# Sheet1.net
KiCad netlist of a schematic drawn in Altium Designer
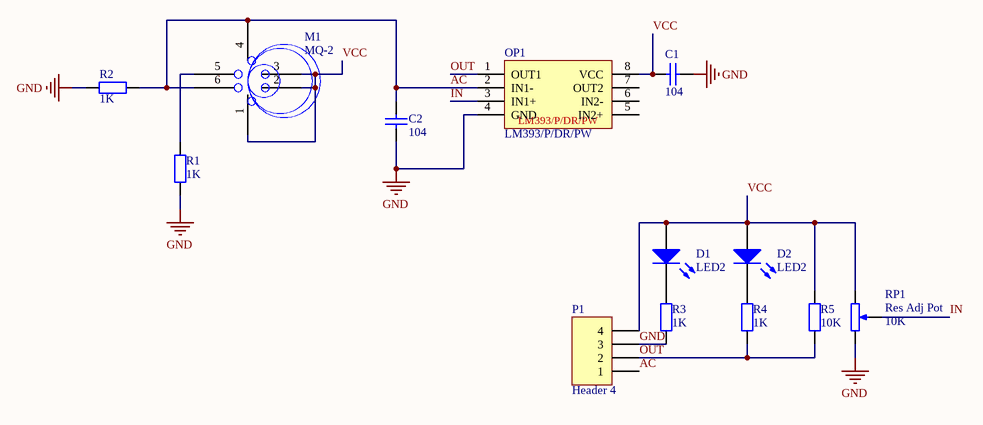
[diagram p0: Sheet1.SchDoc]

(export (version "E")
  (design (tool "Eeschema 10.0.6"))
  (components
    (comp (ref "C1")
      (value "104")
      (footprint "CC2012-0805")
      (description "Polarized Capacitor (Radial)")
      (fields (field (name "Comment") "Cap Chip 0805") (field (name "PUBLISHER") "Altium Limited"))
      (libsource (lib "EButterflyIntegratedLibrary") (part "Cap Chip 0805"))
    )
    (comp (ref "C2")
      (value "104")
      (footprint "CC2012-0805")
      (description "Polarized Capacitor (Radial)")
      (fields (field (name "Comment") "Cap Chip 0805") (field (name "PUBLISHER") "Altium Limited"))
      (libsource (lib "EButterflyIntegratedLibrary") (part "Cap Chip 0805"))
    )
    (comp (ref "D1")
      (value "LED2")
      (footprint "3.2X1.6X1.1")
      (description "Typical RED, GREEN, YELLOW, AMBER GaAs LED")
      (fields (field (name "PUBLISHER") "Altium Limited"))
      (libsource (lib "Miscellaneous Devices") (part "LED2"))
    )
    (comp (ref "D2")
      (value "LED2")
      (footprint "3.2X1.6X1.1")
      (description "Typical RED, GREEN, YELLOW, AMBER GaAs LED")
      (fields (field (name "PUBLISHER") "Altium Limited"))
      (libsource (lib "Miscellaneous Devices") (part "LED2"))
    )
    (comp (ref "M1") (value "MQ-2") (footprint "PCBComponent_1") (libsource (lib "传感器") (part "MQ-2")))
    (comp (ref "OP1")
      (value "LM393/P/DR/PW")
      (footprint "DIP-8")
      (libsource (lib "运放器件") (part "LM393/P/DR/PW"))
    )
    (comp (ref "P1")
      (value "Header 4")
      (footprint "HDR1X4")
      (description "Header, 4-Pin")
      (fields (field (name "PUBLISHER") "Altium Limited"))
      (libsource (lib "Miscellaneous Connectors") (part "Header 4"))
    )
    (comp (ref "R1")
      (value "1K")
      (footprint "CR2012-0805")
      (description "Resistor")
      (fields (field (name "Comment") "Resistor Chip 0805") (field (name "PUBLISHER") "Altium Limited"))
      (libsource (lib "EButterflyIntegratedLibrary") (part "Resistor Chip 0805"))
    )
    (comp (ref "R2")
      (value "1K")
      (footprint "CR2012-0805")
      (description "Resistor")
      (fields (field (name "Comment") "Resistor Chip 0805") (field (name "PUBLISHER") "Altium Limited"))
      (libsource (lib "") (part "Resistor Chip 0805_1"))
    )
    (comp (ref "R3")
      (value "1K")
      (footprint "CR2012-0805")
      (description "Resistor")
      (fields (field (name "Comment") "Resistor Chip 0805") (field (name "PUBLISHER") "Altium Limited"))
      (libsource (lib "EButterflyIntegratedLibrary") (part "Resistor Chip 0805"))
    )
    (comp (ref "R4")
      (value "1K")
      (footprint "CR2012-0805")
      (description "Resistor")
      (fields (field (name "Comment") "Resistor Chip 0805") (field (name "PUBLISHER") "Altium Limited"))
      (libsource (lib "EButterflyIntegratedLibrary") (part "Resistor Chip 0805"))
    )
    (comp (ref "R5")
      (value "10K")
      (footprint "CR2012-0805")
      (description "Resistor")
      (fields (field (name "Comment") "Resistor Chip 0805") (field (name "PUBLISHER") "Altium Limited"))
      (libsource (lib "EButterflyIntegratedLibrary") (part "Resistor Chip 0805"))
    )
    (comp (ref "RP1")
      (value "Res Adj Pot")
      (footprint "POT BIG")
      (description "Potentiometer")
      (fields (field (name "ALTIUM_VALUE") "10K") (field (name "PUBLISHER") "Altium Limited"))
      (libsource (lib "EButterflyIntegratedLibrary") (part "Res Adj Pot"))
    )
  )
  (nets
    (net (code "1") (name "/AC") (class "Default")
      (node (ref "C2") (pin "2") (pinfunction "2_2") (pintype "passive"))
      (node (ref "M1") (pin "4") (pinfunction "H2_4") (pintype "passive"))
      (node (ref "M1") (pin "6") (pinfunction "B2_6") (pintype "passive"))
      (node (ref "OP1") (pin "2") (pinfunction "IN1-_2") (pintype "open_emitter"))
      (node (ref "P1") (pin "1") (pinfunction "1_1") (pintype "passive"))
      (node (ref "R2") (pin "2") (pinfunction "2_2") (pintype "passive"))
    )
    (net (code "2") (name "/IN") (class "Default")
      (node (ref "OP1") (pin "3") (pinfunction "IN1+_3") (pintype "open_emitter"))
      (node (ref "RP1") (pin "3") (pinfunction "TAP_3") (pintype "passive"))
    )
    (net (code "3") (name "/OUT") (class "Default")
      (node (ref "OP1") (pin "1") (pinfunction "OUT1_1") (pintype "open_emitter"))
      (node (ref "P1") (pin "2") (pinfunction "2_2") (pintype "passive"))
      (node (ref "R4") (pin "1") (pinfunction "1_1") (pintype "passive"))
      (node (ref "R5") (pin "1") (pinfunction "1_1") (pintype "passive"))
    )
    (net (code "4") (name "/VCC") (class "Default")
      (node (ref "C1") (pin "1") (pinfunction "1_1") (pintype "passive"))
      (node (ref "D1") (pin "1") (pinfunction "A_1") (pintype "passive"))
      (node (ref "D2") (pin "1") (pinfunction "A_1") (pintype "passive"))
      (node (ref "M1") (pin "1") (pinfunction "H1_1") (pintype "passive"))
      (node (ref "M1") (pin "2") (pinfunction "2_2") (pintype "passive"))
      (node (ref "M1") (pin "3") (pinfunction "A1_3") (pintype "passive"))
      (node (ref "OP1") (pin "8") (pinfunction "VCC_8") (pintype "open_emitter"))
      (node (ref "P1") (pin "4") (pinfunction "4_4") (pintype "passive"))
      (node (ref "R5") (pin "2") (pinfunction "2_2") (pintype "passive"))
      (node (ref "RP1") (pin "2") (pinfunction "BOT_2") (pintype "passive"))
    )
    (net (code "5") (name "GND") (class "Default")
      (node (ref "C1") (pin "2") (pinfunction "2_2") (pintype "passive"))
      (node (ref "C2") (pin "1") (pinfunction "1_1") (pintype "passive"))
      (node (ref "OP1") (pin "4") (pinfunction "GND_4") (pintype "open_emitter"))
      (node (ref "P1") (pin "3") (pinfunction "3_3") (pintype "passive"))
      (node (ref "R1") (pin "1") (pinfunction "1_1") (pintype "passive"))
      (node (ref "R2") (pin "1") (pinfunction "1_1") (pintype "passive"))
      (node (ref "R3") (pin "1") (pinfunction "1_1") (pintype "passive"))
      (node (ref "RP1") (pin "1") (pinfunction "TOP_1") (pintype "passive"))
    )
    (net (code "6") (name "Net-(D1-K)") (class "Default")
      (node (ref "D1") (pin "2") (pinfunction "K_2") (pintype "passive"))
      (node (ref "R3") (pin "2") (pinfunction "2_2") (pintype "passive"))
    )
    (net (code "7") (name "Net-(D2-K)") (class "Default")
      (node (ref "D2") (pin "2") (pinfunction "K_2") (pintype "passive"))
      (node (ref "R4") (pin "2") (pinfunction "2_2") (pintype "passive"))
    )
    (net (code "8") (name "Net-(M1-A2)") (class "Default")
      (node (ref "M1") (pin "5") (pinfunction "A2_5") (pintype "passive"))
      (node (ref "R1") (pin "2") (pinfunction "2_2") (pintype "passive"))
    )
    (net (code "9") (name "unconnected-(OP1-IN2+-Pad5)") (class "Default")
      (node (ref "OP1") (pin "5") (pinfunction "IN2+_5") (pintype "open_emitter"))
    )
    (net (code "10") (name "unconnected-(OP1-IN2--Pad6)") (class "Default")
      (node (ref "OP1") (pin "6") (pinfunction "IN2-_6") (pintype "open_emitter"))
    )
    (net (code "11") (name "unconnected-(OP1-OUT2-Pad7)") (class "Default")
      (node (ref "OP1") (pin "7") (pinfunction "OUT2_7") (pintype "open_emitter"))
    )
  )
)
